# S7CAS-PLEIADES-CARTE-MERE_P02_POWER.net
KiCad netlist of a schematic drawn in Altium Designer
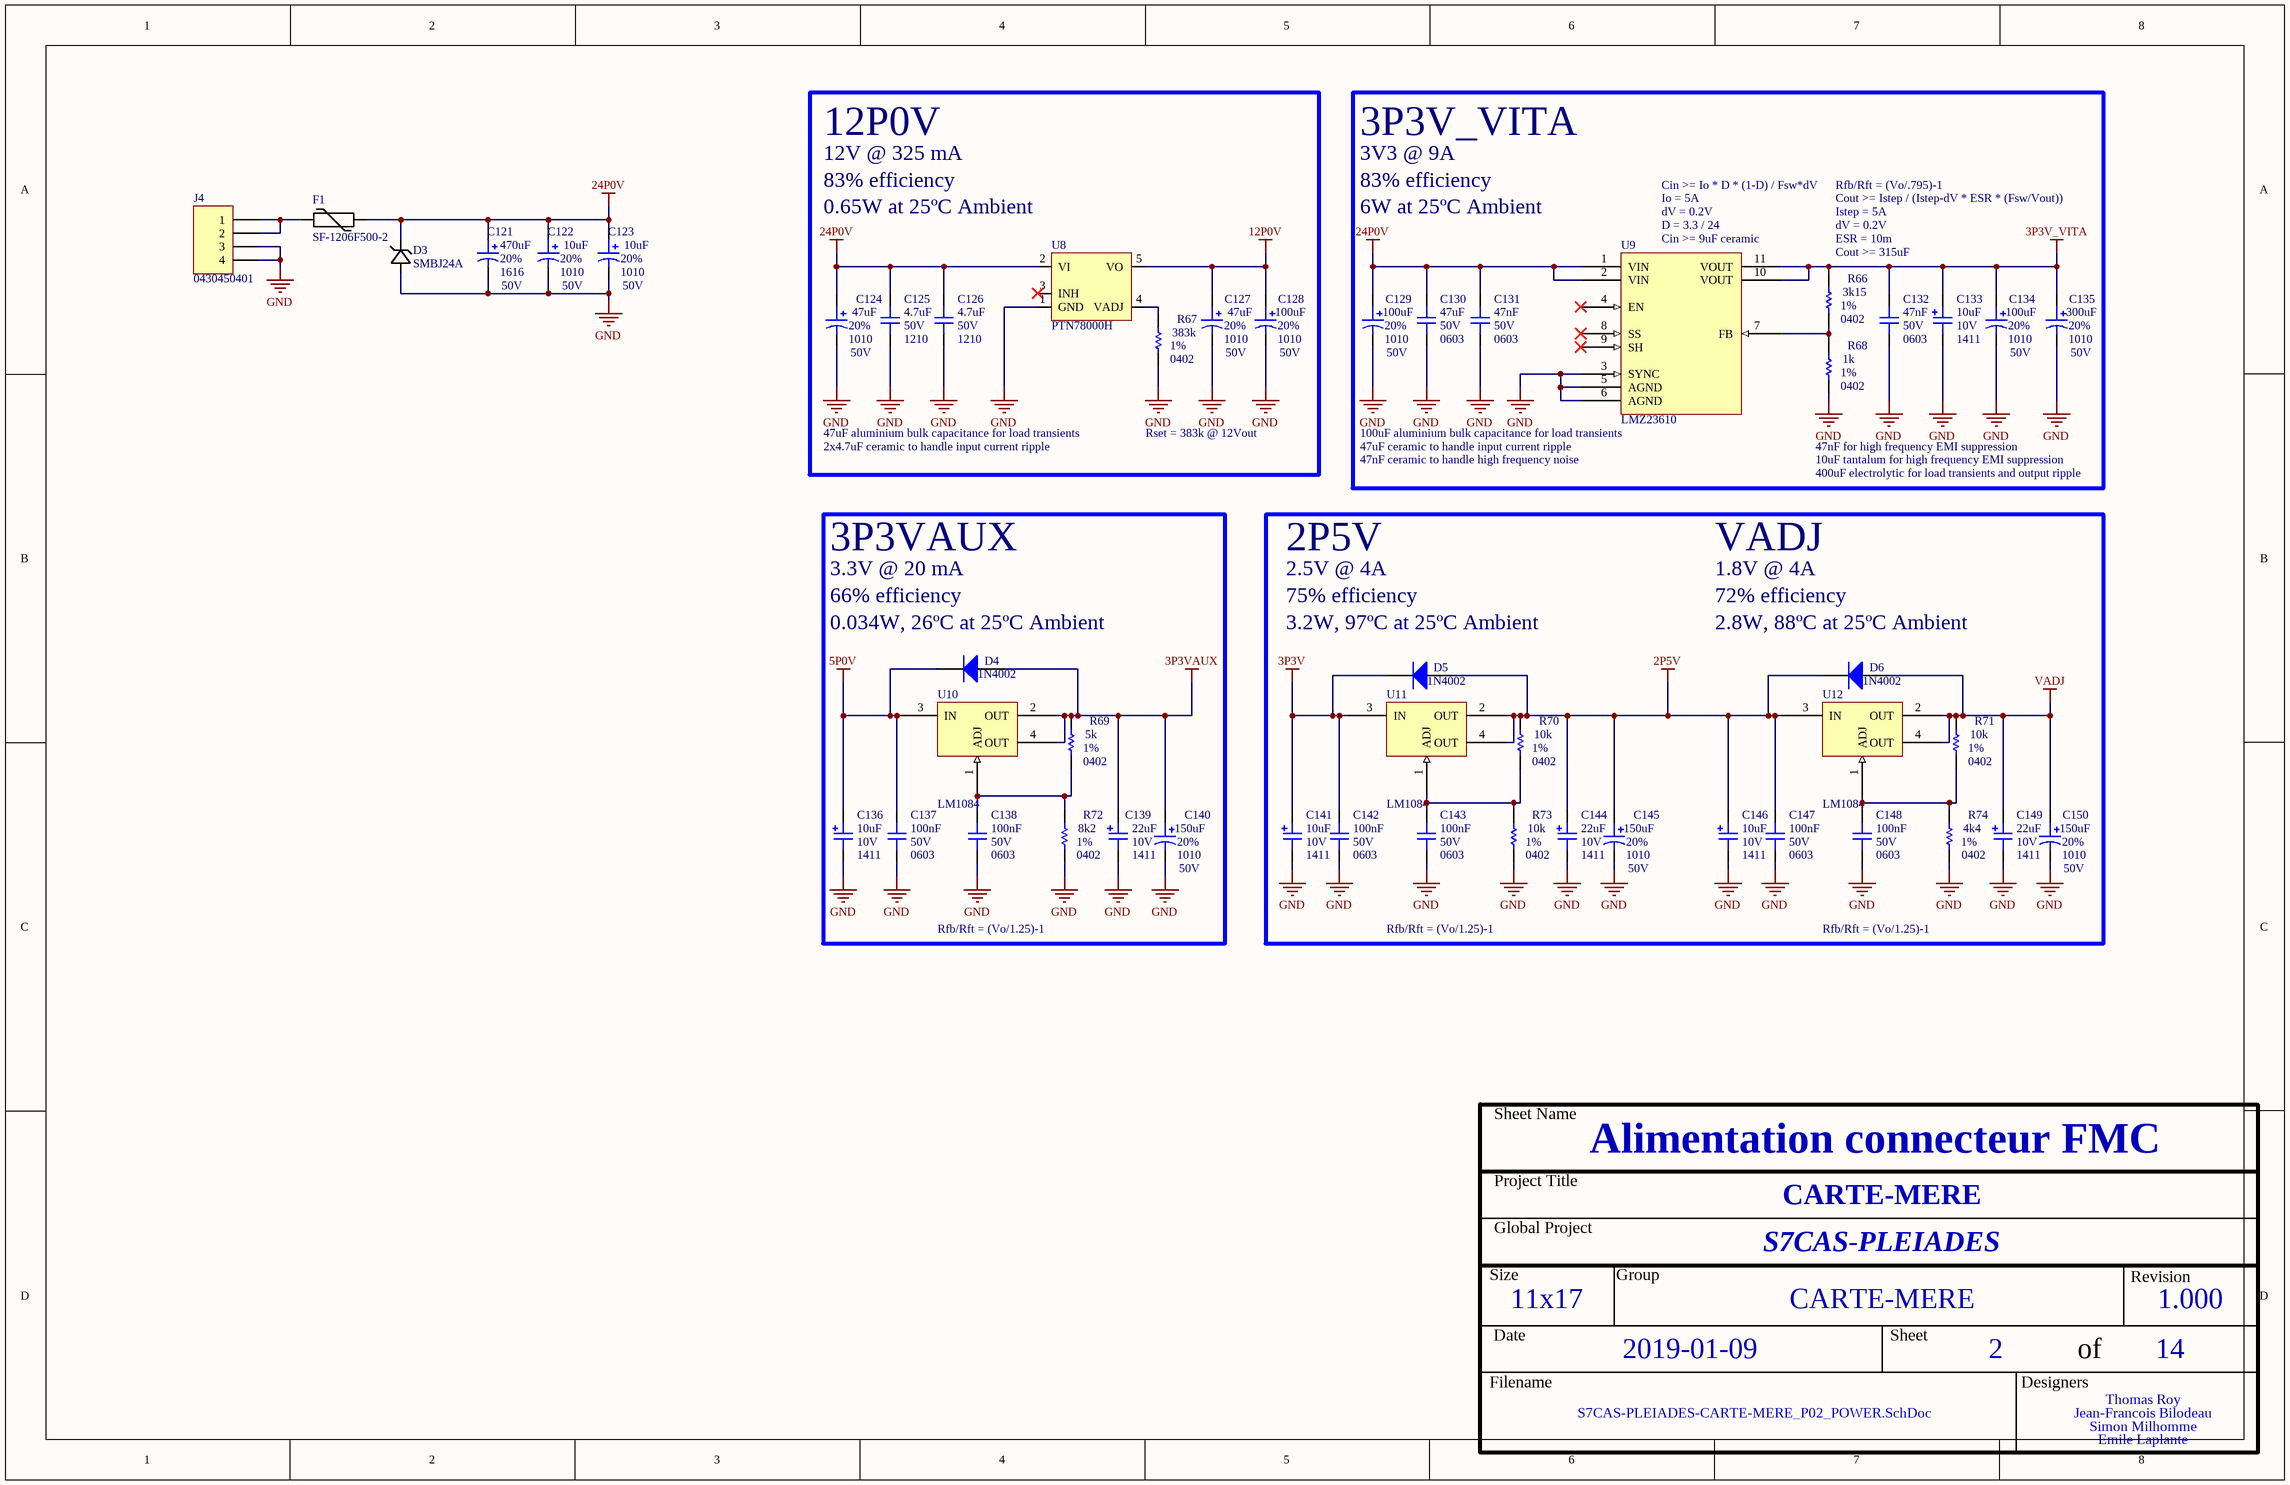
[diagram p0: S7CAS-PLEIADES-CARTE-MERE_P02_POWER.SchDoc]

(export (version "E")
  (design (tool "Eeschema 10.0.6"))
  (components
    (comp (ref "C121")
      (value "470uF")
      (footprint "CAP_ALU_1616_vishay")
      (description "CAP - ALU 470uF 20% 50V - 1616")
      (fields
        (field (name "MFG") "Vishay Dale")
        (field (name "MFG PART NUMBER") "MAL214699108E3")
        (field (name "VOLTAGE") "50V")
        (field (name "PACKAGE") "1616")
        (field (name "PRECISION") "20%")
        (field (name "CREATEDBY") "Jonathan Bouchard")
      )
      (libsource (lib "S7CAS_Lib2019_REV1_00") (part "CAP_ALU_MAL214699108E3"))
    )
    (comp (ref "C122")
      (value "10uF")
      (footprint "CAP_ALU_1010_vishay")
      (description "CAP - ALU 100uF 20% 50V - 1010")
      (fields
        (field (name "MFG") "Vishay Dale")
        (field (name "MFG PART NUMBER") "MAL215099101E3")
        (field (name "VOLTAGE") "50V")
        (field (name "PACKAGE") "1010")
        (field (name "PRECISION") "20%")
        (field (name "CREATEDBY") "Jonathan Bouchard")
      )
      (libsource (lib "S7CAS_Lib2019_REV1_00") (part "CAP_ALU_MAL215099101E3"))
    )
    (comp (ref "C123")
      (value "10uF")
      (footprint "CAP_ALU_1010_vishay")
      (description "CAP - ALU 100uF 20% 50V - 1010")
      (fields
        (field (name "MFG") "Vishay Dale")
        (field (name "MFG PART NUMBER") "MAL215099101E3")
        (field (name "VOLTAGE") "50V")
        (field (name "PACKAGE") "1010")
        (field (name "PRECISION") "20%")
        (field (name "CREATEDBY") "Jonathan Bouchard")
      )
      (libsource (lib "S7CAS_Lib2019_REV1_00") (part "CAP_ALU_MAL215099101E3"))
    )
    (comp (ref "C124")
      (value "47uF")
      (footprint "CAP_ALU_1010_vishay")
      (description "CAP - ALU 47uF 20% 50V - 1010")
      (fields
        (field (name "MFG") "Vishay Dale")
        (field (name "MFG PART NUMBER") "MAL215099101E3")
        (field (name "VOLTAGE") "50V")
        (field (name "PACKAGE") "1010")
        (field (name "PRECISION") "20%")
        (field (name "CREATEDBY") "Jonathan Bouchard")
      )
      (libsource (lib "S7CAS_Lib2019_REV1_00") (part "CAP_ALU_MAL215099101E3"))
    )
    (comp (ref "C125")
      (value "4.7uF")
      (footprint "CAP_1210")
      (description "CAP - 1210")
      (fields
        (field (name "VOLTAGE") "50V")
        (field (name "PACKAGE") "1210")
        (field (name "CREATEDBY") "Jonathan Bouchard")
      )
      (libsource (lib "S7CAS_Lib2019_REV1_00") (part "CAP - 1210"))
    )
    (comp (ref "C126")
      (value "4.7uF")
      (footprint "CAP_1210")
      (description "CAP - 1210")
      (fields
        (field (name "VOLTAGE") "50V")
        (field (name "PACKAGE") "1210")
        (field (name "CREATEDBY") "Jonathan Bouchard")
      )
      (libsource (lib "S7CAS_Lib2019_REV1_00") (part "CAP - 1210"))
    )
    (comp (ref "C127")
      (value "47uF")
      (footprint "CAP_ALU_1010_vishay")
      (description "CAP - ALU 47uF 20% 50V - 1010")
      (fields
        (field (name "MFG") "Vishay Dale")
        (field (name "MFG PART NUMBER") "MAL215099101E3")
        (field (name "VOLTAGE") "50V")
        (field (name "PACKAGE") "1010")
        (field (name "PRECISION") "20%")
        (field (name "CREATEDBY") "Jonathan Bouchard")
      )
      (libsource (lib "S7CAS_Lib2019_REV1_00") (part "CAP_ALU_MAL215099101E3"))
    )
    (comp (ref "C128")
      (value "100uF")
      (footprint "CAP_ALU_1010_vishay")
      (description "CAP - ALU 100uF 20% 50V - 1010")
      (fields
        (field (name "MFG") "Vishay Dale")
        (field (name "MFG PART NUMBER") "MAL215099101E3")
        (field (name "VOLTAGE") "50V")
        (field (name "PACKAGE") "1010")
        (field (name "PRECISION") "20%")
        (field (name "CREATEDBY") "Jonathan Bouchard")
      )
      (libsource (lib "S7CAS_Lib2019_REV1_00") (part "CAP_ALU_MAL215099101E3"))
    )
    (comp (ref "C129")
      (value "100uF")
      (footprint "CAP_ALU_1010_vishay")
      (description "CAP - ALU 100uF 20% 50V - 1010")
      (fields
        (field (name "MFG") "Vishay Dale")
        (field (name "MFG PART NUMBER") "MAL215099101E3")
        (field (name "VOLTAGE") "50V")
        (field (name "PACKAGE") "1010")
        (field (name "PRECISION") "20%")
        (field (name "CREATEDBY") "Jonathan Bouchard")
      )
      (libsource (lib "S7CAS_Lib2019_REV1_00") (part "CAP_ALU_MAL215099101E3"))
    )
    (comp (ref "C130")
      (value "47uF")
      (footprint "CAP_0603")
      (description "CAP - 0603")
      (fields
        (field (name "VOLTAGE") "50V")
        (field (name "PACKAGE") "0603")
        (field (name "CREATEDBY") "Jonathan Bouchard")
      )
      (libsource (lib "S7CAS_Lib2019_REV1_00") (part "CAP - 0603"))
    )
    (comp (ref "C131")
      (value "47nF")
      (footprint "CAP_0603")
      (description "CAP - 0603")
      (fields
        (field (name "VOLTAGE") "50V")
        (field (name "PACKAGE") "0603")
        (field (name "CREATEDBY") "Jonathan Bouchard")
      )
      (libsource (lib "S7CAS_Lib2019_REV1_00") (part "CAP - 0603"))
    )
    (comp (ref "C132")
      (value "47nF")
      (footprint "CAP_0603")
      (description "CAP - 0603")
      (fields
        (field (name "VOLTAGE") "50V")
        (field (name "PACKAGE") "0603")
        (field (name "CREATEDBY") "Jonathan Bouchard")
      )
      (libsource (lib "S7CAS_Lib2019_REV1_00") (part "CAP - 0603"))
    )
    (comp (ref "C133")
      (value "10uF")
      (footprint "CAP_TAN_1411(B)")
      (description "CAP - TANTALUM - 1411")
      (fields
        (field (name "VOLTAGE") "10V")
        (field (name "PACKAGE") "1411")
        (field (name "Comment") "CAP - TANTALUM - CASE B")
        (field (name "CREATEDBY") "Jonathan Bouchard")
      )
      (libsource (lib "S7CAS_Lib2019_REV1_00") (part "CAP_TANT_1411(B)"))
    )
    (comp (ref "C134")
      (value "100uF")
      (footprint "CAP_ALU_1010_vishay")
      (description "CAP - ALU 100uF 20% 50V - 1010")
      (fields
        (field (name "MFG") "Vishay Dale")
        (field (name "MFG PART NUMBER") "MAL215099101E3")
        (field (name "VOLTAGE") "50V")
        (field (name "PACKAGE") "1010")
        (field (name "PRECISION") "20%")
        (field (name "CREATEDBY") "Jonathan Bouchard")
      )
      (libsource (lib "S7CAS_Lib2019_REV1_00") (part "CAP_ALU_MAL215099101E3"))
    )
    (comp (ref "C135")
      (value "300uF")
      (footprint "CAP_ALU_1010_vishay")
      (description "CAP - ALU 100uF 20% 50V - 1010")
      (fields
        (field (name "MFG") "Vishay Dale")
        (field (name "MFG PART NUMBER") "MAL215099101E3")
        (field (name "VOLTAGE") "50V")
        (field (name "PACKAGE") "1010")
        (field (name "PRECISION") "20%")
        (field (name "CREATEDBY") "Jonathan Bouchard")
      )
      (libsource (lib "S7CAS_Lib2019_REV1_00") (part "CAP_ALU_MAL215099101E3"))
    )
    (comp (ref "C136")
      (value "10uF")
      (footprint "CAP_TAN_1411(B)")
      (description "CAP - TANTALUM - 1411")
      (fields
        (field (name "VOLTAGE") "10V")
        (field (name "PACKAGE") "1411")
        (field (name "Comment") "CAP - TANTALUM - CASE B")
        (field (name "CREATEDBY") "Jonathan Bouchard")
      )
      (libsource (lib "S7CAS_Lib2019_REV1_00") (part "CAP_TANT_1411(B)"))
    )
    (comp (ref "C137")
      (value "100nF")
      (footprint "CAP_0603")
      (description "CAP - 0603")
      (fields
        (field (name "VOLTAGE") "50V")
        (field (name "PACKAGE") "0603")
        (field (name "CREATEDBY") "Jonathan Bouchard")
      )
      (libsource (lib "S7CAS_Lib2019_REV1_00") (part "CAP - 0603"))
    )
    (comp (ref "C138")
      (value "100nF")
      (footprint "CAP_0603")
      (description "CAP - 0603")
      (fields
        (field (name "VOLTAGE") "50V")
        (field (name "PACKAGE") "0603")
        (field (name "CREATEDBY") "Jonathan Bouchard")
      )
      (libsource (lib "S7CAS_Lib2019_REV1_00") (part "CAP - 0603"))
    )
    (comp (ref "C139")
      (value "22uF")
      (footprint "CAP_TAN_1411(B)")
      (description "CAP - TANTALUM - 1411")
      (fields
        (field (name "VOLTAGE") "10V")
        (field (name "PACKAGE") "1411")
        (field (name "Comment") "CAP - TANTALUM - CASE B")
        (field (name "CREATEDBY") "Jonathan Bouchard")
      )
      (libsource (lib "S7CAS_Lib2019_REV1_00") (part "CAP_TANT_1411(B)"))
    )
    (comp (ref "C140")
      (value "150uF")
      (footprint "CAP_ALU_1010_vishay")
      (description "CAP - ALU 100uF 20% 50V - 1010")
      (fields
        (field (name "MFG") "Vishay Dale")
        (field (name "MFG PART NUMBER") "MAL215099101E3")
        (field (name "VOLTAGE") "50V")
        (field (name "PACKAGE") "1010")
        (field (name "PRECISION") "20%")
        (field (name "CREATEDBY") "Jonathan Bouchard")
      )
      (libsource (lib "S7CAS_Lib2019_REV1_00") (part "CAP_ALU_MAL215099101E3"))
    )
    (comp (ref "C141")
      (value "10uF")
      (footprint "CAP_TAN_1411(B)")
      (description "CAP - TANTALUM - 1411")
      (fields
        (field (name "VOLTAGE") "10V")
        (field (name "PACKAGE") "1411")
        (field (name "Comment") "CAP - TANTALUM - CASE B")
        (field (name "CREATEDBY") "Jonathan Bouchard")
      )
      (libsource (lib "S7CAS_Lib2019_REV1_00") (part "CAP_TANT_1411(B)"))
    )
    (comp (ref "C142")
      (value "100nF")
      (footprint "CAP_0603")
      (description "CAP - 0603")
      (fields
        (field (name "VOLTAGE") "50V")
        (field (name "PACKAGE") "0603")
        (field (name "CREATEDBY") "Jonathan Bouchard")
      )
      (libsource (lib "S7CAS_Lib2019_REV1_00") (part "CAP - 0603"))
    )
    (comp (ref "C143")
      (value "100nF")
      (footprint "CAP_0603")
      (description "CAP - 0603")
      (fields
        (field (name "VOLTAGE") "50V")
        (field (name "PACKAGE") "0603")
        (field (name "CREATEDBY") "Jonathan Bouchard")
      )
      (libsource (lib "S7CAS_Lib2019_REV1_00") (part "CAP - 0603"))
    )
    (comp (ref "C144")
      (value "22uF")
      (footprint "CAP_TAN_1411(B)")
      (description "CAP - TANTALUM - 1411")
      (fields
        (field (name "VOLTAGE") "10V")
        (field (name "PACKAGE") "1411")
        (field (name "Comment") "CAP - TANTALUM - CASE B")
        (field (name "CREATEDBY") "Jonathan Bouchard")
      )
      (libsource (lib "S7CAS_Lib2019_REV1_00") (part "CAP_TANT_1411(B)"))
    )
    (comp (ref "C145")
      (value "150uF")
      (footprint "CAP_ALU_1010_vishay")
      (description "CAP - ALU 100uF 20% 50V - 1010")
      (fields
        (field (name "MFG") "Vishay Dale")
        (field (name "MFG PART NUMBER") "MAL215099101E3")
        (field (name "VOLTAGE") "50V")
        (field (name "PACKAGE") "1010")
        (field (name "PRECISION") "20%")
        (field (name "CREATEDBY") "Jonathan Bouchard")
      )
      (libsource (lib "S7CAS_Lib2019_REV1_00") (part "CAP_ALU_MAL215099101E3"))
    )
    (comp (ref "C146")
      (value "10uF")
      (footprint "CAP_TAN_1411(B)")
      (description "CAP - TANTALUM - 1411")
      (fields
        (field (name "VOLTAGE") "10V")
        (field (name "PACKAGE") "1411")
        (field (name "Comment") "CAP - TANTALUM - CASE B")
        (field (name "CREATEDBY") "Jonathan Bouchard")
      )
      (libsource (lib "S7CAS_Lib2019_REV1_00") (part "CAP_TANT_1411(B)"))
    )
    (comp (ref "C147")
      (value "100nF")
      (footprint "CAP_0603")
      (description "CAP - 0603")
      (fields
        (field (name "VOLTAGE") "50V")
        (field (name "PACKAGE") "0603")
        (field (name "CREATEDBY") "Jonathan Bouchard")
      )
      (libsource (lib "S7CAS_Lib2019_REV1_00") (part "CAP - 0603"))
    )
    (comp (ref "C148")
      (value "100nF")
      (footprint "CAP_0603")
      (description "CAP - 0603")
      (fields
        (field (name "VOLTAGE") "50V")
        (field (name "PACKAGE") "0603")
        (field (name "CREATEDBY") "Jonathan Bouchard")
      )
      (libsource (lib "S7CAS_Lib2019_REV1_00") (part "CAP - 0603"))
    )
    (comp (ref "C149")
      (value "22uF")
      (footprint "CAP_TAN_1411(B)")
      (description "CAP - TANTALUM - 1411")
      (fields
        (field (name "VOLTAGE") "10V")
        (field (name "PACKAGE") "1411")
        (field (name "Comment") "CAP - TANTALUM - CASE B")
        (field (name "CREATEDBY") "Jonathan Bouchard")
      )
      (libsource (lib "S7CAS_Lib2019_REV1_00") (part "CAP_TANT_1411(B)"))
    )
    (comp (ref "C150")
      (value "150uF")
      (footprint "CAP_ALU_1010_vishay")
      (description "CAP - ALU 100uF 20% 50V - 1010")
      (fields
        (field (name "MFG") "Vishay Dale")
        (field (name "MFG PART NUMBER") "MAL215099101E3")
        (field (name "VOLTAGE") "50V")
        (field (name "PACKAGE") "1010")
        (field (name "PRECISION") "20%")
        (field (name "CREATEDBY") "Jonathan Bouchard")
      )
      (libsource (lib "S7CAS_Lib2019_REV1_00") (part "CAP_ALU_MAL215099101E3"))
    )
    (comp (ref "D3")
      (value "SMBJ24A")
      (footprint "DO-214AA")
      (libsource (lib "TempLibrary") (part "SMBJ24A"))
    )
    (comp (ref "D4")
      (value "1N4002")
      (footprint "DO-41")
      (description "1 Amp General Purpose Rectifier")
      (fields (field (name "PUBLISHER") "Altium Limited"))
      (libsource (lib "Miscellaneous Devices") (part "Diode 1N4002"))
    )
    (comp (ref "D5")
      (value "1N4002")
      (footprint "DO-41")
      (description "1 Amp General Purpose Rectifier")
      (fields (field (name "PUBLISHER") "Altium Limited"))
      (libsource (lib "Miscellaneous Devices") (part "Diode 1N4002"))
    )
    (comp (ref "D6")
      (value "1N4002")
      (footprint "DO-41")
      (description "1 Amp General Purpose Rectifier")
      (fields (field (name "PUBLISHER") "Altium Limited"))
      (libsource (lib "Miscellaneous Devices") (part "Diode 1N4002"))
    )
    (comp (ref "F1")
      (value "SF-1206F500-2")
      (footprint "RES_1206")
      (fields (field (name "VOLTAGE") "24V") (field (name "MANUFACTURER") "Bourns Inc."))
      (libsource (lib "TempLibrary") (part "SF-1206F500-2"))
    )
    (comp (ref "J4")
      (value "0430450401")
      (footprint "0430450401")
      (description "Header, 4-Pin")
      (fields (field (name "MANUFACTURER") "Molex") (field (name "PUBLISHER") "Altium Limited"))
      (libsource (lib "Miscellaneous Connectors") (part "Header 4"))
    )
    (comp (ref "R66")
      (value "3k15")
      (footprint "RES_0402")
      (description "RES - 0402")
      (fields
        (field (name "VOLTAGE") "50V")
        (field (name "POWER") "1/16W")
        (field (name "PACKAGE") "0402")
        (field (name "PRECISION") "1%")
        (field (name "CREATEDBY") "Jonathan Bouchard")
      )
      (libsource (lib "S7CAS_Lib2019_REV1_00") (part "RES - 0402"))
    )
    (comp (ref "R67")
      (value "383k")
      (footprint "RES_0402")
      (description "RES - 0402 - 1/16W")
      (fields
        (field (name "VOLTAGE") "50V")
        (field (name "POWER") "1/16W")
        (field (name "PACKAGE") "0402")
        (field (name "PRECISION") "1%")
        (field (name "CREATEDBY") "Jonathan Bouchard")
      )
      (libsource (lib "S7CAS_Lib2019_REV1_00") (part "RES - 0402"))
    )
    (comp (ref "R68")
      (value "1k")
      (footprint "RES_0402")
      (description "RES - 0402")
      (fields
        (field (name "VOLTAGE") "50V")
        (field (name "POWER") "1/16W")
        (field (name "PACKAGE") "0402")
        (field (name "PRECISION") "1%")
        (field (name "CREATEDBY") "Jonathan Bouchard")
      )
      (libsource (lib "S7CAS_Lib2019_REV1_00") (part "RES - 0402"))
    )
    (comp (ref "R69")
      (value "5k")
      (footprint "RES_0402")
      (description "RES - 0402")
      (fields
        (field (name "VOLTAGE") "50V")
        (field (name "POWER") "1/16W")
        (field (name "PACKAGE") "0402")
        (field (name "PRECISION") "1%")
        (field (name "CREATEDBY") "Jonathan Bouchard")
      )
      (libsource (lib "S7CAS_Lib2019_REV1_00") (part "RES - 0402"))
    )
    (comp (ref "R70")
      (value "10k")
      (footprint "RES_0402")
      (description "RES - 0402")
      (fields
        (field (name "VOLTAGE") "50V")
        (field (name "POWER") "1/16W")
        (field (name "PACKAGE") "0402")
        (field (name "PRECISION") "1%")
        (field (name "CREATEDBY") "Jonathan Bouchard")
      )
      (libsource (lib "S7CAS_Lib2019_REV1_00") (part "RES - 0402"))
    )
    (comp (ref "R71")
      (value "10k")
      (footprint "RES_0402")
      (description "RES - 0402")
      (fields
        (field (name "VOLTAGE") "50V")
        (field (name "POWER") "1/16W")
        (field (name "PACKAGE") "0402")
        (field (name "PRECISION") "1%")
        (field (name "CREATEDBY") "Jonathan Bouchard")
      )
      (libsource (lib "S7CAS_Lib2019_REV1_00") (part "RES - 0402"))
    )
    (comp (ref "R72")
      (value "8k2")
      (footprint "RES_0402")
      (description "RES - 0402")
      (fields
        (field (name "VOLTAGE") "50V")
        (field (name "POWER") "1/16W")
        (field (name "PACKAGE") "0402")
        (field (name "PRECISION") "1%")
        (field (name "CREATEDBY") "Jonathan Bouchard")
      )
      (libsource (lib "S7CAS_Lib2019_REV1_00") (part "RES - 0402"))
    )
    (comp (ref "R73")
      (value "10k")
      (footprint "RES_0402")
      (description "RES - 0402")
      (fields
        (field (name "VOLTAGE") "50V")
        (field (name "POWER") "1/16W")
        (field (name "PACKAGE") "0402")
        (field (name "PRECISION") "1%")
        (field (name "CREATEDBY") "Jonathan Bouchard")
      )
      (libsource (lib "S7CAS_Lib2019_REV1_00") (part "RES - 0402"))
    )
    (comp (ref "R74")
      (value "4k4")
      (footprint "RES_0402")
      (description "RES - 0402")
      (fields
        (field (name "VOLTAGE") "50V")
        (field (name "POWER") "1/16W")
        (field (name "PACKAGE") "0402")
        (field (name "PRECISION") "1%")
        (field (name "CREATEDBY") "Jonathan Bouchard")
      )
      (libsource (lib "S7CAS_Lib2019_REV1_00") (part "RES - 0402"))
    )
    (comp (ref "U8")
      (value "PTN78000H")
      (footprint "PTN78000W")
      (description "XXX - 1.5-A,\r\nWIDE-INPUT\r\nADJUSTABLE\r\nSWITCHING\r\nREGULATOR - Package")
      (libsource (lib "lib_Thom") (part "PTN78000H"))
    )
    (comp (ref "U9") (value "LMZ23610") (footprint "NDY0011A") (libsource (lib "lib_JF") (part "LMZ23610")))
    (comp (ref "U10") (value "LM1084") (footprint "DPAK-3") (libsource (lib "lib_JF") (part "LM1084")))
    (comp (ref "U11") (value "LM1084") (footprint "DPAK-3") (libsource (lib "lib_JF") (part "LM1084")))
    (comp (ref "U12") (value "LM1084") (footprint "DPAK-3") (libsource (lib "lib_JF") (part "LM1084")))
  )
  (nets
    (net (code "1") (name "2P5V") (class "Default")
      (node (ref "C144") (pin "2") (pinfunction "2_2") (pintype "passive"))
      (node (ref "C145") (pin "1") (pinfunction "1_1") (pintype "passive"))
      (node (ref "C146") (pin "2") (pinfunction "2_2") (pintype "passive"))
      (node (ref "C147") (pin "2") (pinfunction "2_2") (pintype "passive"))
      (node (ref "D5") (pin "1") (pinfunction "A_1") (pintype "passive"))
      (node (ref "D6") (pin "2") (pinfunction "K_2") (pintype "passive"))
      (node (ref "R70") (pin "2") (pinfunction "2_2") (pintype "passive"))
      (node (ref "U11") (pin "2") (pinfunction "OUT_2") (pintype "power_in"))
      (node (ref "U11") (pin "4") (pinfunction "OUT_4") (pintype "power_in"))
      (node (ref "U12") (pin "3") (pinfunction "IN_3") (pintype "power_in"))
    )
    (net (code "2") (name "3P3V") (class "Default")
      (node (ref "C141") (pin "2") (pinfunction "2_2") (pintype "passive"))
      (node (ref "C142") (pin "2") (pinfunction "2_2") (pintype "passive"))
      (node (ref "D5") (pin "2") (pinfunction "K_2") (pintype "passive"))
      (node (ref "U11") (pin "3") (pinfunction "IN_3") (pintype "power_in"))
    )
    (net (code "3") (name "3P3VAUX") (class "Default")
      (node (ref "C139") (pin "2") (pinfunction "2_2") (pintype "passive"))
      (node (ref "C140") (pin "1") (pinfunction "1_1") (pintype "passive"))
      (node (ref "D4") (pin "1") (pinfunction "A_1") (pintype "passive"))
      (node (ref "R69") (pin "2") (pinfunction "2_2") (pintype "passive"))
      (node (ref "U10") (pin "2") (pinfunction "OUT_2") (pintype "power_in"))
      (node (ref "U10") (pin "4") (pinfunction "OUT_4") (pintype "power_in"))
    )
    (net (code "4") (name "3P3V_VITA") (class "Default")
      (node (ref "C132") (pin "2") (pinfunction "2_2") (pintype "passive"))
      (node (ref "C133") (pin "2") (pinfunction "2_2") (pintype "passive"))
      (node (ref "C134") (pin "1") (pinfunction "1_1") (pintype "passive"))
      (node (ref "C135") (pin "1") (pinfunction "1_1") (pintype "passive"))
      (node (ref "R66") (pin "2") (pinfunction "2_2") (pintype "passive"))
      (node (ref "U9") (pin "10") (pinfunction "VOUT_10") (pintype "power_in"))
      (node (ref "U9") (pin "11") (pinfunction "VOUT_11") (pintype "power_in"))
    )
    (net (code "5") (name "5P0V") (class "Default")
      (node (ref "C136") (pin "2") (pinfunction "2_2") (pintype "passive"))
      (node (ref "C137") (pin "2") (pinfunction "2_2") (pintype "passive"))
      (node (ref "D4") (pin "2") (pinfunction "K_2") (pintype "passive"))
      (node (ref "U10") (pin "3") (pinfunction "IN_3") (pintype "power_in"))
    )
    (net (code "6") (name "12P0V") (class "Default")
      (node (ref "C127") (pin "1") (pinfunction "1_1") (pintype "passive"))
      (node (ref "C128") (pin "1") (pinfunction "1_1") (pintype "passive"))
      (node (ref "U8") (pin "5") (pinfunction "VO_5") (pintype "passive"))
    )
    (net (code "7") (name "24P0V") (class "Default")
      (node (ref "C121") (pin "1") (pinfunction "1_1") (pintype "passive"))
      (node (ref "C122") (pin "1") (pinfunction "1_1") (pintype "passive"))
      (node (ref "C123") (pin "1") (pinfunction "1_1") (pintype "passive"))
      (node (ref "C124") (pin "1") (pinfunction "1_1") (pintype "passive"))
      (node (ref "C125") (pin "2") (pinfunction "2_2") (pintype "passive"))
      (node (ref "C126") (pin "2") (pinfunction "2_2") (pintype "passive"))
      (node (ref "C129") (pin "1") (pinfunction "1_1") (pintype "passive"))
      (node (ref "C130") (pin "2") (pinfunction "2_2") (pintype "passive"))
      (node (ref "C131") (pin "2") (pinfunction "2_2") (pintype "passive"))
      (node (ref "D3") (pin "1") (pinfunction "C_1") (pintype "passive"))
      (node (ref "F1") (pin "2") (pinfunction "2_2") (pintype "passive"))
      (node (ref "U8") (pin "2") (pinfunction "VI_2") (pintype "passive"))
      (node (ref "U9") (pin "1") (pinfunction "VIN_1") (pintype "power_in"))
      (node (ref "U9") (pin "2") (pinfunction "VIN_2") (pintype "power_in"))
    )
    (net (code "8") (name "GND") (class "Default")
      (node (ref "C121") (pin "2") (pinfunction "2_2") (pintype "passive"))
      (node (ref "C122") (pin "2") (pinfunction "2_2") (pintype "passive"))
      (node (ref "C123") (pin "2") (pinfunction "2_2") (pintype "passive"))
      (node (ref "C124") (pin "2") (pinfunction "2_2") (pintype "passive"))
      (node (ref "C125") (pin "1") (pinfunction "1_1") (pintype "passive"))
      (node (ref "C126") (pin "1") (pinfunction "1_1") (pintype "passive"))
      (node (ref "C127") (pin "2") (pinfunction "2_2") (pintype "passive"))
      (node (ref "C128") (pin "2") (pinfunction "2_2") (pintype "passive"))
      (node (ref "C129") (pin "2") (pinfunction "2_2") (pintype "passive"))
      (node (ref "C130") (pin "1") (pinfunction "1_1") (pintype "passive"))
      (node (ref "C131") (pin "1") (pinfunction "1_1") (pintype "passive"))
      (node (ref "C132") (pin "1") (pinfunction "1_1") (pintype "passive"))
      (node (ref "C133") (pin "1") (pinfunction "1_1") (pintype "passive"))
      (node (ref "C134") (pin "2") (pinfunction "2_2") (pintype "passive"))
      (node (ref "C135") (pin "2") (pinfunction "2_2") (pintype "passive"))
      (node (ref "C136") (pin "1") (pinfunction "1_1") (pintype "passive"))
      (node (ref "C137") (pin "1") (pinfunction "1_1") (pintype "passive"))
      (node (ref "C138") (pin "1") (pinfunction "1_1") (pintype "passive"))
      (node (ref "C139") (pin "1") (pinfunction "1_1") (pintype "passive"))
      (node (ref "C140") (pin "2") (pinfunction "2_2") (pintype "passive"))
      (node (ref "C141") (pin "1") (pinfunction "1_1") (pintype "passive"))
      (node (ref "C142") (pin "1") (pinfunction "1_1") (pintype "passive"))
      (node (ref "C143") (pin "1") (pinfunction "1_1") (pintype "passive"))
      (node (ref "C144") (pin "1") (pinfunction "1_1") (pintype "passive"))
      (node (ref "C145") (pin "2") (pinfunction "2_2") (pintype "passive"))
      (node (ref "C146") (pin "1") (pinfunction "1_1") (pintype "passive"))
      (node (ref "C147") (pin "1") (pinfunction "1_1") (pintype "passive"))
      (node (ref "C148") (pin "1") (pinfunction "1_1") (pintype "passive"))
      (node (ref "C149") (pin "1") (pinfunction "1_1") (pintype "passive"))
      (node (ref "C150") (pin "2") (pinfunction "2_2") (pintype "passive"))
      (node (ref "D3") (pin "2") (pinfunction "A_2") (pintype "passive"))
      (node (ref "J4") (pin "3") (pinfunction "3_3") (pintype "passive"))
      (node (ref "J4") (pin "4") (pinfunction "4_4") (pintype "passive"))
      (node (ref "R67") (pin "1") (pinfunction "1_1") (pintype "passive"))
      (node (ref "R68") (pin "1") (pinfunction "1_1") (pintype "passive"))
      (node (ref "R72") (pin "1") (pinfunction "1_1") (pintype "passive"))
      (node (ref "R73") (pin "1") (pinfunction "1_1") (pintype "passive"))
      (node (ref "R74") (pin "1") (pinfunction "1_1") (pintype "passive"))
      (node (ref "U8") (pin "1") (pinfunction "GND_1") (pintype "passive"))
      (node (ref "U9") (pin "3") (pinfunction "SYNC_3") (pintype "input"))
      (node (ref "U9") (pin "5") (pinfunction "AGND_5") (pintype "power_in"))
      (node (ref "U9") (pin "6") (pinfunction "AGND_6") (pintype "power_in"))
    )
    (net (code "9") (name "Net-(F1-Pad1)") (class "Default")
      (node (ref "F1") (pin "1") (pinfunction "1_1") (pintype "passive"))
      (node (ref "J4") (pin "1") (pinfunction "1_1") (pintype "passive"))
      (node (ref "J4") (pin "2") (pinfunction "2_2") (pintype "passive"))
    )
    (net (code "10") (name "Net-(U8-VADJ)") (class "Default")
      (node (ref "R67") (pin "2") (pinfunction "2_2") (pintype "passive"))
      (node (ref "U8") (pin "4") (pinfunction "VADJ_4") (pintype "passive"))
    )
    (net (code "11") (name "Net-(U9-FB)") (class "Default")
      (node (ref "R66") (pin "1") (pinfunction "1_1") (pintype "passive"))
      (node (ref "R68") (pin "2") (pinfunction "2_2") (pintype "passive"))
      (node (ref "U9") (pin "7") (pinfunction "FB_7") (pintype "input"))
    )
    (net (code "12") (name "Net-(U10-ADJ)") (class "Default")
      (node (ref "C138") (pin "2") (pinfunction "2_2") (pintype "passive"))
      (node (ref "R69") (pin "1") (pinfunction "1_1") (pintype "passive"))
      (node (ref "R72") (pin "2") (pinfunction "2_2") (pintype "passive"))
      (node (ref "U10") (pin "1") (pinfunction "ADJ_1") (pintype "input"))
    )
    (net (code "13") (name "Net-(U11-ADJ)") (class "Default")
      (node (ref "C143") (pin "2") (pinfunction "2_2") (pintype "passive"))
      (node (ref "R70") (pin "1") (pinfunction "1_1") (pintype "passive"))
      (node (ref "R73") (pin "2") (pinfunction "2_2") (pintype "passive"))
      (node (ref "U11") (pin "1") (pinfunction "ADJ_1") (pintype "input"))
    )
    (net (code "14") (name "Net-(U12-ADJ)") (class "Default")
      (node (ref "C148") (pin "2") (pinfunction "2_2") (pintype "passive"))
      (node (ref "R71") (pin "1") (pinfunction "1_1") (pintype "passive"))
      (node (ref "R74") (pin "2") (pinfunction "2_2") (pintype "passive"))
      (node (ref "U12") (pin "1") (pinfunction "ADJ_1") (pintype "input"))
    )
    (net (code "15") (name "VADJ") (class "Default")
      (node (ref "C149") (pin "2") (pinfunction "2_2") (pintype "passive"))
      (node (ref "C150") (pin "1") (pinfunction "1_1") (pintype "passive"))
      (node (ref "D6") (pin "1") (pinfunction "A_1") (pintype "passive"))
      (node (ref "R71") (pin "2") (pinfunction "2_2") (pintype "passive"))
      (node (ref "U12") (pin "2") (pinfunction "OUT_2") (pintype "power_in"))
      (node (ref "U12") (pin "4") (pinfunction "OUT_4") (pintype "power_in"))
    )
    (net (code "16") (name "unconnected-(U8-INH-Pad3)") (class "Default")
      (node (ref "U8") (pin "3") (pinfunction "INH_3") (pintype "passive+no_connect"))
    )
    (net (code "17") (name "unconnected-(U9-EN-Pad4)") (class "Default")
      (node (ref "U9") (pin "4") (pinfunction "EN_4") (pintype "input+no_connect"))
    )
    (net (code "18") (name "unconnected-(U9-SH-Pad9)") (class "Default")
      (node (ref "U9") (pin "9") (pinfunction "SH_9") (pintype "input+no_connect"))
    )
    (net (code "19") (name "unconnected-(U9-SS-Pad8)") (class "Default")
      (node (ref "U9") (pin "8") (pinfunction "SS_8") (pintype "input+no_connect"))
    )
  )
)
